# atxpi.net
KiCad netlist of a schematic drawn in EAGLE
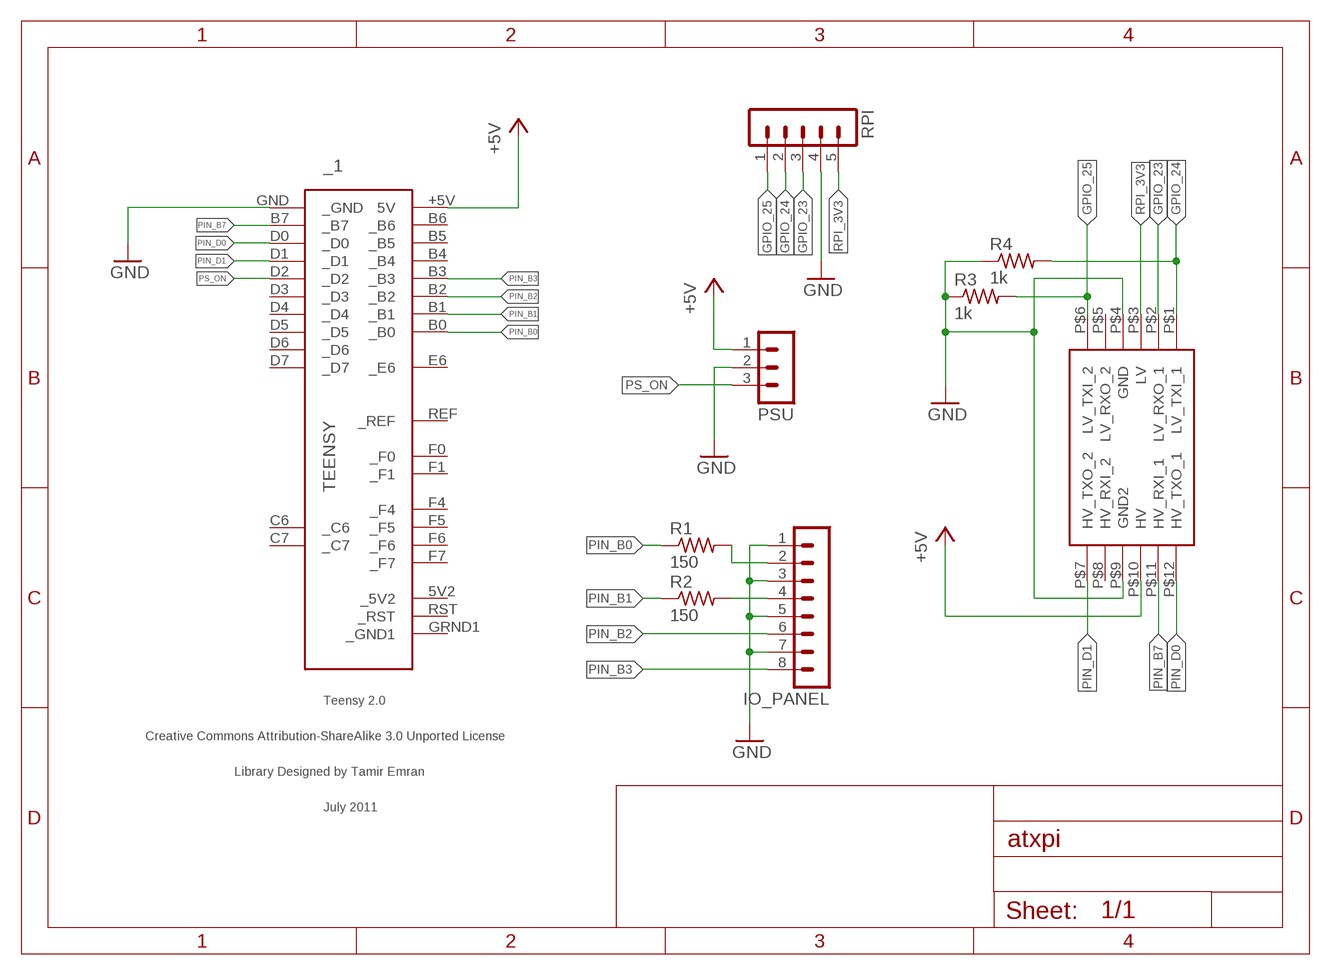
[diagram p0: schematic, sheet 1]

(export (version "E")
  (design (tool "Eeschema 10.0.6"))
  (components
    (comp (ref "IO_PANEL")
      (value "MA08-1")
      (footprint "eagle-import:MA08-1")
      (libsource (lib "eagle-import") (part "MA08-1"))
    )
    (comp (ref "PSU")
      (value "MA03-1")
      (footprint "eagle-import:MA03-1")
      (libsource (lib "eagle-import") (part "MA03-1"))
    )
    (comp (ref "R1")
      (value "150")
      (footprint "eagle-import:0309_12")
      (libsource (lib "eagle-import") (part "R-US_0309/12"))
    )
    (comp (ref "R2")
      (value "150")
      (footprint "eagle-import:0309_12")
      (libsource (lib "eagle-import") (part "R-US_0309/12"))
    )
    (comp (ref "R3")
      (value "1k")
      (footprint "eagle-import:0309_12")
      (libsource (lib "eagle-import") (part "resistor_R-US_0309/12"))
    )
    (comp (ref "R4")
      (value "1k")
      (footprint "eagle-import:0309_12")
      (libsource (lib "eagle-import") (part "resistor_R-US_0309/12"))
    )
    (comp (ref "RPI")
      (value "MA05-1")
      (footprint "eagle-import:MA05-1")
      (libsource (lib "eagle-import") (part "MA05-1"))
    )
    (comp (ref "U$1")
      (value "LOGIC_LEVEL_CONVERTER")
      (footprint "eagle-import:LOGIC_LEVEL_CONVERTER")
      (libsource (lib "eagle-import") (part "LOGIC_LEVEL_CONVERTER"))
    )
    (comp (ref "_1")
      (value "TEENSY")
      (footprint "eagle-import:TEENSY")
      (libsource (lib "eagle-import") (part "TEENSY"))
    )
  )
  (nets
    (net (code "1") (name "+5V") (class "Default")
      (node (ref "PSU") (pin "1") (pinfunction "1_1") (pintype "passive"))
      (node (ref "U$1") (pin "P$10") (pinfunction "HV_P$10") (pintype "bidirectional"))
      (node (ref "_1") (pin "+5V") (pinfunction "5V_+5V") (pintype "bidirectional"))
    )
    (net (code "2") (name "GND") (class "Default")
      (node (ref "IO_PANEL") (pin "1") (pinfunction "1_1") (pintype "passive"))
      (node (ref "IO_PANEL") (pin "3") (pinfunction "3_3") (pintype "passive"))
      (node (ref "IO_PANEL") (pin "5") (pinfunction "5_5") (pintype "passive"))
      (node (ref "IO_PANEL") (pin "7") (pinfunction "7_7") (pintype "passive"))
      (node (ref "PSU") (pin "2") (pinfunction "2_2") (pintype "passive"))
      (node (ref "R3") (pin "1") (pinfunction "1_1") (pintype "passive"))
      (node (ref "R4") (pin "1") (pinfunction "1_1") (pintype "passive"))
      (node (ref "RPI") (pin "4") (pinfunction "4_4") (pintype "passive"))
      (node (ref "U$1") (pin "P$4") (pinfunction "GND_P$4") (pintype "bidirectional"))
      (node (ref "U$1") (pin "P$9") (pinfunction "GND2_P$9") (pintype "bidirectional"))
      (node (ref "_1") (pin "GND") (pinfunction "_GND_GND") (pintype "bidirectional"))
    )
    (net (code "3") (name "GPIO_23") (class "Default")
      (node (ref "RPI") (pin "3") (pinfunction "3_3") (pintype "passive"))
      (node (ref "U$1") (pin "P$2") (pinfunction "LV_RXO_1_P$2") (pintype "bidirectional"))
    )
    (net (code "4") (name "GPIO_24") (class "Default")
      (node (ref "R4") (pin "2") (pinfunction "2_2") (pintype "passive"))
      (node (ref "RPI") (pin "2") (pinfunction "2_2") (pintype "passive"))
      (node (ref "U$1") (pin "P$1") (pinfunction "LV_TXI_1_P$1") (pintype "bidirectional"))
    )
    (net (code "5") (name "GPIO_25") (class "Default")
      (node (ref "R3") (pin "2") (pinfunction "2_2") (pintype "passive"))
      (node (ref "RPI") (pin "1") (pinfunction "1_1") (pintype "passive"))
      (node (ref "U$1") (pin "P$6") (pinfunction "LV_TXI_2_P$6") (pintype "bidirectional"))
    )
    (net (code "6") (name "Net-(IO_PANEL-Pad2)") (class "Default")
      (node (ref "IO_PANEL") (pin "2") (pinfunction "2_2") (pintype "passive"))
      (node (ref "R1") (pin "2") (pinfunction "2_2") (pintype "passive"))
    )
    (net (code "7") (name "Net-(IO_PANEL-Pad4)") (class "Default")
      (node (ref "IO_PANEL") (pin "4") (pinfunction "4_4") (pintype "passive"))
      (node (ref "R2") (pin "2") (pinfunction "2_2") (pintype "passive"))
    )
    (net (code "8") (name "PIN_B0") (class "Default")
      (node (ref "R1") (pin "1") (pinfunction "1_1") (pintype "passive"))
      (node (ref "_1") (pin "B0") (pinfunction "_B0_B0") (pintype "bidirectional"))
    )
    (net (code "9") (name "PIN_B1") (class "Default")
      (node (ref "R2") (pin "1") (pinfunction "1_1") (pintype "passive"))
      (node (ref "_1") (pin "B1") (pinfunction "_B1_B1") (pintype "bidirectional"))
    )
    (net (code "10") (name "PIN_B2") (class "Default")
      (node (ref "IO_PANEL") (pin "6") (pinfunction "6_6") (pintype "passive"))
      (node (ref "_1") (pin "B2") (pinfunction "_B2_B2") (pintype "bidirectional"))
    )
    (net (code "11") (name "PIN_B3") (class "Default")
      (node (ref "IO_PANEL") (pin "8") (pinfunction "8_8") (pintype "passive"))
      (node (ref "_1") (pin "B3") (pinfunction "_B3_B3") (pintype "bidirectional"))
    )
    (net (code "12") (name "PIN_B7") (class "Default")
      (node (ref "U$1") (pin "P$11") (pinfunction "HV_RXI_1_P$11") (pintype "bidirectional"))
      (node (ref "_1") (pin "B7") (pinfunction "_B7_B7") (pintype "bidirectional"))
    )
    (net (code "13") (name "PIN_D0") (class "Default")
      (node (ref "U$1") (pin "P$12") (pinfunction "HV_TXO_1_P$12") (pintype "bidirectional"))
      (node (ref "_1") (pin "D0") (pinfunction "_D0_D0") (pintype "bidirectional"))
    )
    (net (code "14") (name "PIN_D1") (class "Default")
      (node (ref "U$1") (pin "P$7") (pinfunction "HV_TXO_2_P$7") (pintype "bidirectional"))
      (node (ref "_1") (pin "D1") (pinfunction "_D1_D1") (pintype "bidirectional"))
    )
    (net (code "15") (name "PS_ON") (class "Default")
      (node (ref "PSU") (pin "3") (pinfunction "3_3") (pintype "passive"))
      (node (ref "_1") (pin "D2") (pinfunction "_D2_D2") (pintype "bidirectional"))
    )
    (net (code "16") (name "RPI_3V3") (class "Default")
      (node (ref "RPI") (pin "5") (pinfunction "5_5") (pintype "passive"))
      (node (ref "U$1") (pin "P$3") (pinfunction "LV_P$3") (pintype "bidirectional"))
    )
    (net (code "17") (name "unconnected-(U$1-HV_RXI_2-PadP$8)") (class "Default")
      (node (ref "U$1") (pin "P$8") (pinfunction "HV_RXI_2_P$8") (pintype "bidirectional"))
    )
    (net (code "18") (name "unconnected-(U$1-LV_RXO_2-PadP$5)") (class "Default")
      (node (ref "U$1") (pin "P$5") (pinfunction "LV_RXO_2_P$5") (pintype "bidirectional"))
    )
    (net (code "19") (name "unconnected-(_1-_5V2-Pad5V2)") (class "Default")
      (node (ref "_1") (pin "5V2") (pinfunction "_5V2_5V2") (pintype "bidirectional"))
    )
    (net (code "20") (name "unconnected-(_1-_B4-PadB4)") (class "Default")
      (node (ref "_1") (pin "B4") (pinfunction "_B4_B4") (pintype "bidirectional"))
    )
    (net (code "21") (name "unconnected-(_1-_B5-PadB5)") (class "Default")
      (node (ref "_1") (pin "B5") (pinfunction "_B5_B5") (pintype "bidirectional"))
    )
    (net (code "22") (name "unconnected-(_1-_B6-PadB6)") (class "Default")
      (node (ref "_1") (pin "B6") (pinfunction "_B6_B6") (pintype "bidirectional"))
    )
    (net (code "23") (name "unconnected-(_1-_C6-PadC6)") (class "Default")
      (node (ref "_1") (pin "C6") (pinfunction "_C6_C6") (pintype "bidirectional"))
    )
    (net (code "24") (name "unconnected-(_1-_C7-PadC7)") (class "Default")
      (node (ref "_1") (pin "C7") (pinfunction "_C7_C7") (pintype "bidirectional"))
    )
    (net (code "25") (name "unconnected-(_1-_D3-PadD3)") (class "Default")
      (node (ref "_1") (pin "D3") (pinfunction "_D3_D3") (pintype "bidirectional"))
    )
    (net (code "26") (name "unconnected-(_1-_D4-PadD4)") (class "Default")
      (node (ref "_1") (pin "D4") (pinfunction "_D4_D4") (pintype "bidirectional"))
    )
    (net (code "27") (name "unconnected-(_1-_D5-PadD5)") (class "Default")
      (node (ref "_1") (pin "D5") (pinfunction "_D5_D5") (pintype "bidirectional"))
    )
    (net (code "28") (name "unconnected-(_1-_D6-PadD6)") (class "Default")
      (node (ref "_1") (pin "D6") (pinfunction "_D6_D6") (pintype "bidirectional"))
    )
    (net (code "29") (name "unconnected-(_1-_D7-PadD7)") (class "Default")
      (node (ref "_1") (pin "D7") (pinfunction "_D7_D7") (pintype "bidirectional"))
    )
    (net (code "30") (name "unconnected-(_1-_E6-PadE6)") (class "Default")
      (node (ref "_1") (pin "E6") (pinfunction "_E6_E6") (pintype "bidirectional"))
    )
    (net (code "31") (name "unconnected-(_1-_F0-PadF0)") (class "Default")
      (node (ref "_1") (pin "F0") (pinfunction "_F0_F0") (pintype "bidirectional"))
    )
    (net (code "32") (name "unconnected-(_1-_F1-PadF1)") (class "Default")
      (node (ref "_1") (pin "F1") (pinfunction "_F1_F1") (pintype "bidirectional"))
    )
    (net (code "33") (name "unconnected-(_1-_F4-PadF4)") (class "Default")
      (node (ref "_1") (pin "F4") (pinfunction "_F4_F4") (pintype "bidirectional"))
    )
    (net (code "34") (name "unconnected-(_1-_F5-PadF5)") (class "Default")
      (node (ref "_1") (pin "F5") (pinfunction "_F5_F5") (pintype "bidirectional"))
    )
    (net (code "35") (name "unconnected-(_1-_F6-PadF6)") (class "Default")
      (node (ref "_1") (pin "F6") (pinfunction "_F6_F6") (pintype "bidirectional"))
    )
    (net (code "36") (name "unconnected-(_1-_F7-PadF7)") (class "Default")
      (node (ref "_1") (pin "F7") (pinfunction "_F7_F7") (pintype "bidirectional"))
    )
    (net (code "37") (name "unconnected-(_1-_GND1-PadGRND1)") (class "Default")
      (node (ref "_1") (pin "GRND1") (pinfunction "_GND1_GRND1") (pintype "bidirectional"))
    )
    (net (code "38") (name "unconnected-(_1-_REF-PadREF)") (class "Default")
      (node (ref "_1") (pin "REF") (pinfunction "_REF_REF") (pintype "bidirectional"))
    )
    (net (code "39") (name "unconnected-(_1-_RST-PadRST)") (class "Default")
      (node (ref "_1") (pin "RST") (pinfunction "_RST_RST") (pintype "bidirectional"))
    )
  )
)
